# transciever.net
KiCad netlist of a schematic drawn in EAGLE
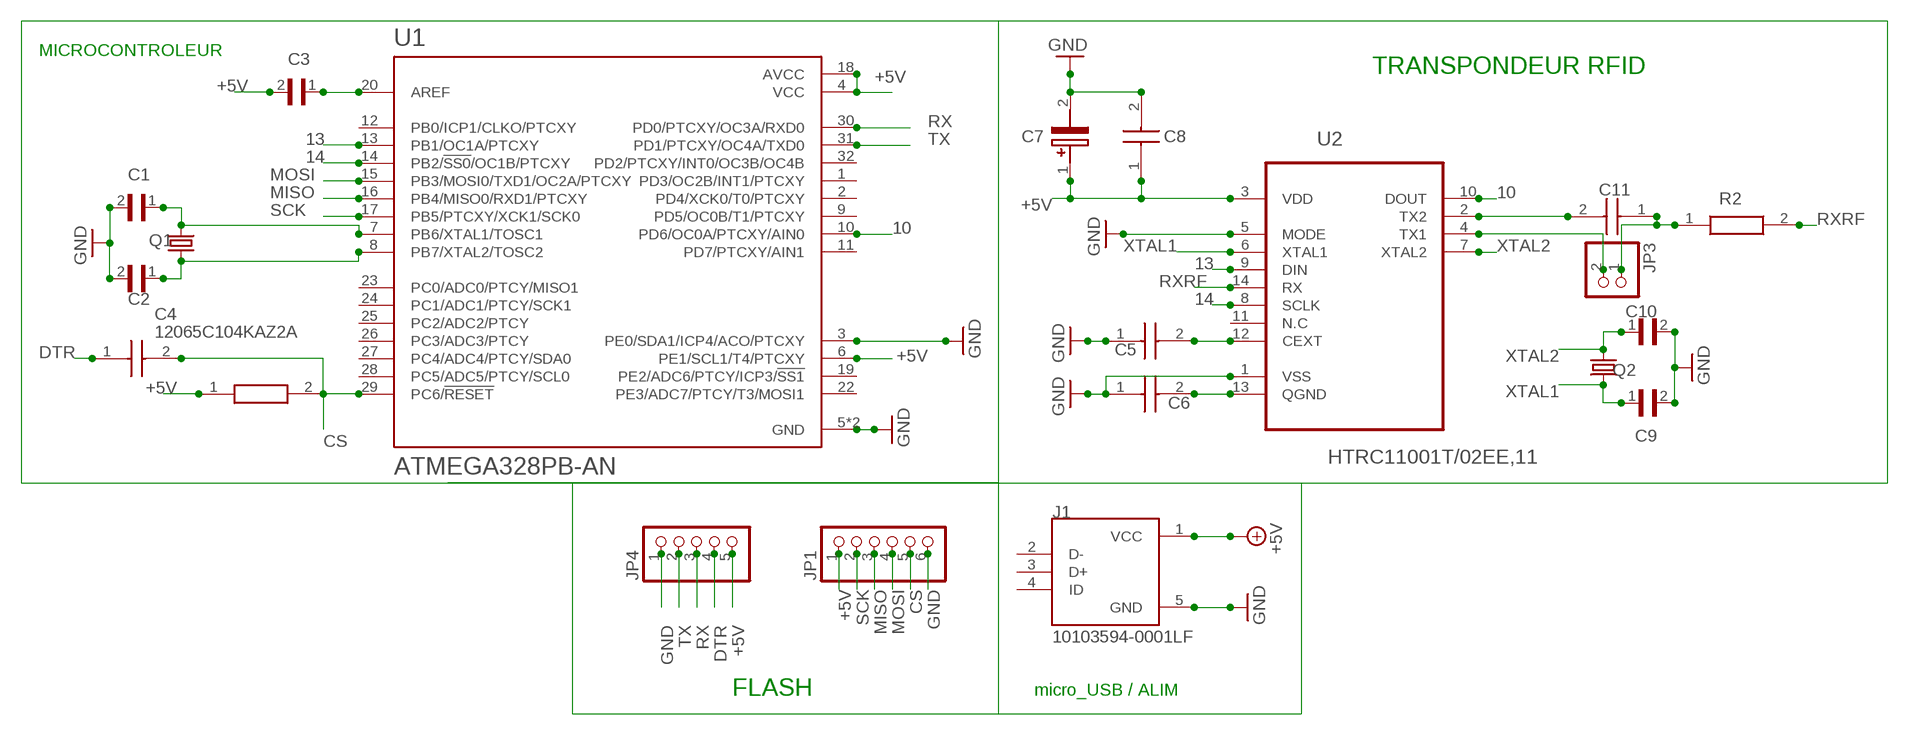
[diagram p0: schematic, sheet 1]

(export (version "E")
  (design (tool "Eeschema 10.0.6"))
  (components
    (comp (ref "C1")
      (value "06031U220GAT2A")
      (footprint "eagle-import:CAPC1608X90")
      (libsource (lib "eagle-import") (part "06031U220GAT2A"))
    )
    (comp (ref "C2")
      (value "06031U220GAT2A")
      (footprint "eagle-import:CAPC1608X90")
      (libsource (lib "eagle-import") (part "06031U220GAT2A"))
    )
    (comp (ref "C3")
      (value "GRT31CC80J476KE13L")
      (footprint "eagle-import:CAP3216X125N")
      (libsource (lib "eagle-import") (part "GRT31CC80J476KE13L"))
    )
    (comp (ref "C4")
      (value "12065C104KAZ2A")
      (footprint "eagle-import:CAPC3216X94N")
      (fields (field (name "RS_PART_NUMBER") "6983673"))
      (libsource (lib "eagle-import") (part "12065C104KAZ2A"))
    )
    (comp (ref "C5")
      (value "12065C104KAZ2A")
      (footprint "eagle-import:CAPC3216X94N")
      (fields (field (name "RS_PART_NUMBER") "6983673"))
      (libsource (lib "eagle-import") (part "12065C104KAZ2A"))
    )
    (comp (ref "C6")
      (value "12065C104KAZ2A")
      (footprint "eagle-import:CAPC3216X94N")
      (fields (field (name "RS_PART_NUMBER") "6983673"))
      (libsource (lib "eagle-import") (part "12065C104KAZ2A"))
    )
    (comp (ref "C7")
      (value "NACE100M16V4X5.5TR13F")
      (footprint "eagle-import:NACE(4X5.5)")
      (fields (field (name "RS_PART_NUMBER") "7379625P"))
      (libsource (lib "eagle-import") (part "NACE100M16V4X5.5TR13F"))
    )
    (comp (ref "C8")
      (value "12065C104KAZ2A")
      (footprint "eagle-import:CAPC3216X94N")
      (fields (field (name "RS_PART_NUMBER") "6983673"))
      (libsource (lib "eagle-import") (part "12065C104KAZ2A"))
    )
    (comp (ref "C9")
      (value "06031U220GAT2A")
      (footprint "eagle-import:CAPC1608X90")
      (libsource (lib "eagle-import") (part "06031U220GAT2A"))
    )
    (comp (ref "C10")
      (value "06031U220GAT2A")
      (footprint "eagle-import:CAPC1608X90")
      (libsource (lib "eagle-import") (part "06031U220GAT2A"))
    )
    (comp (ref "C11")
      (value "12065C104KAZ2A")
      (footprint "eagle-import:CAPC3216X94N")
      (fields (field (name "RS_PART_NUMBER") "6983673"))
      (libsource (lib "eagle-import") (part "12065C104KAZ2A"))
    )
    (comp (ref "J1")
      (value "10103594-0001LF")
      (footprint "eagle-import:FCI_10103594-0001LF")
      (fields (field (name "MANUFACTURER") "Framatome"))
      (libsource (lib "eagle-import") (part "10103594-0001LF"))
    )
    (comp (ref "JP1")
      (value "PINHD-1X6")
      (footprint "eagle-import:1X06")
      (libsource (lib "eagle-import") (part "PINHD-1X6"))
    )
    (comp (ref "JP3")
      (value "PINHD-1X2")
      (footprint "eagle-import:1X02")
      (libsource (lib "eagle-import") (part "PINHD-1X2"))
    )
    (comp (ref "JP4")
      (value "PINHD-1X5")
      (footprint "eagle-import:1X05")
      (libsource (lib "eagle-import") (part "PINHD-1X5"))
    )
    (comp (ref "Q1")
      (value "KX-K")
      (footprint "eagle-import:11.4X4.5")
      (libsource (lib "eagle-import") (part "KX-K"))
    )
    (comp (ref "Q2")
      (value "KX-K")
      (footprint "eagle-import:11.4X4.5")
      (libsource (lib "eagle-import") (part "KX-K"))
    )
    (comp (ref "R1")
      (value "CRCW12061K00FKEA")
      (footprint "eagle-import:RESC3216X60N")
      (fields (field (name "RS_PART_NUMBER") "1694817"))
      (libsource (lib "eagle-import") (part "CRCW12061K00FKEA"))
    )
    (comp (ref "R2")
      (value "CRCW12061K00FKEA")
      (footprint "eagle-import:RESC3216X60N")
      (fields (field (name "RS_PART_NUMBER") "1694817"))
      (libsource (lib "eagle-import") (part "CRCW12061K00FKEA"))
    )
    (comp (ref "U1")
      (value "ATMEGA328PB-AN")
      (footprint "eagle-import:QFP80P900X900X120-32N")
      (fields (field (name "MANUFACTURER") "Microchip"))
      (libsource (lib "eagle-import") (part "ATMEGA328PB-AN"))
    )
    (comp (ref "U2")
      (value "HTRC11001T/02EE,11")
      (footprint "eagle-import:SOIC127P600X175-14N")
      (libsource (lib "eagle-import") (part "HTRC11001T/02EE,11"))
    )
  )
  (nets
    (net (code "1") (name "+5V") (class "Default")
      (node (ref "C3") (pin "2") (pinfunction "2_2") (pintype "passive"))
      (node (ref "C7") (pin "1") (pinfunction "+_1") (pintype "bidirectional"))
      (node (ref "C8") (pin "1") (pinfunction "1_1") (pintype "bidirectional"))
      (node (ref "J1") (pin "1") (pinfunction "VCC_1") (pintype "power_in"))
      (node (ref "JP1") (pin "1") (pinfunction "1_1") (pintype "passive"))
      (node (ref "JP4") (pin "5") (pinfunction "5_5") (pintype "passive"))
      (node (ref "R1") (pin "1") (pinfunction "1_1") (pintype "bidirectional"))
      (node (ref "U1") (pin "18") (pinfunction "AVCC_18") (pintype "power_in"))
      (node (ref "U1") (pin "4") (pinfunction "VCC_4") (pintype "power_in"))
      (node (ref "U1") (pin "6") (pinfunction "PE1/SCL1/T4/PTCXY_6") (pintype "bidirectional"))
      (node (ref "U2") (pin "3") (pinfunction "VDD_3") (pintype "power_in"))
    )
    (net (code "2") (name "/10") (class "Default")
      (node (ref "U1") (pin "10") (pinfunction "PD6/OC0A/PTCXY/AIN0_10") (pintype "bidirectional"))
      (node (ref "U2") (pin "10") (pinfunction "DOUT_10") (pintype "output"))
    )
    (net (code "3") (name "/13") (class "Default")
      (node (ref "U1") (pin "13") (pinfunction "PB1/OC1A/PTCXY_13") (pintype "bidirectional"))
      (node (ref "U2") (pin "9") (pinfunction "DIN_9") (pintype "input"))
    )
    (net (code "4") (name "/14") (class "Default")
      (node (ref "U1") (pin "14") (pinfunction "PB2/~{SS0}/OC1B/PTCXY_14") (pintype "bidirectional"))
      (node (ref "U2") (pin "8") (pinfunction "SCLK_8") (pintype "input"))
    )
    (net (code "5") (name "/CS") (class "Default")
      (node (ref "C4") (pin "2") (pinfunction "2_2") (pintype "bidirectional"))
      (node (ref "JP1") (pin "5") (pinfunction "5_5") (pintype "passive"))
      (node (ref "R1") (pin "2") (pinfunction "2_2") (pintype "bidirectional"))
      (node (ref "U1") (pin "29") (pinfunction "PC6/~{RESET}_29") (pintype "bidirectional"))
    )
    (net (code "6") (name "/DTR") (class "Default")
      (node (ref "C4") (pin "1") (pinfunction "1_1") (pintype "bidirectional"))
      (node (ref "JP4") (pin "4") (pinfunction "4_4") (pintype "passive"))
    )
    (net (code "7") (name "/MISO") (class "Default")
      (node (ref "JP1") (pin "3") (pinfunction "3_3") (pintype "passive"))
      (node (ref "U1") (pin "16") (pinfunction "PB4/MISO0/RXD1/PTCXY_16") (pintype "bidirectional"))
    )
    (net (code "8") (name "/MOSI") (class "Default")
      (node (ref "JP1") (pin "4") (pinfunction "4_4") (pintype "passive"))
      (node (ref "U1") (pin "15") (pinfunction "PB3/MOSI0/TXD1/OC2A/PTCXY_15") (pintype "bidirectional"))
    )
    (net (code "9") (name "/RX") (class "Default")
      (node (ref "JP4") (pin "3") (pinfunction "3_3") (pintype "passive"))
      (node (ref "U1") (pin "30") (pinfunction "PD0/PTCXY/OC3A/RXD0_30") (pintype "bidirectional"))
    )
    (net (code "10") (name "/RXRF") (class "Default")
      (node (ref "R2") (pin "2") (pinfunction "2_2") (pintype "bidirectional"))
      (node (ref "U2") (pin "14") (pinfunction "RX_14") (pintype "input"))
    )
    (net (code "11") (name "/SCK") (class "Default")
      (node (ref "JP1") (pin "2") (pinfunction "2_2") (pintype "passive"))
      (node (ref "U1") (pin "17") (pinfunction "PB5/PTCXY/XCK1/SCK0_17") (pintype "bidirectional"))
    )
    (net (code "12") (name "/TX") (class "Default")
      (node (ref "JP4") (pin "2") (pinfunction "2_2") (pintype "passive"))
      (node (ref "U1") (pin "31") (pinfunction "PD1/PTCXY/OC4A/TXD0_31") (pintype "bidirectional"))
    )
    (net (code "13") (name "/XTAL1") (class "Default")
      (node (ref "C9") (pin "1") (pinfunction "1_1") (pintype "passive"))
      (node (ref "Q2") (pin "2") (pinfunction "2_2") (pintype "passive"))
      (node (ref "U2") (pin "6") (pinfunction "XTAL1_6") (pintype "input"))
    )
    (net (code "14") (name "/XTAL2") (class "Default")
      (node (ref "C10") (pin "1") (pinfunction "1_1") (pintype "passive"))
      (node (ref "Q2") (pin "1") (pinfunction "1_1") (pintype "passive"))
      (node (ref "U2") (pin "7") (pinfunction "XTAL2_7") (pintype "output"))
    )
    (net (code "15") (name "GND") (class "Default")
      (node (ref "C1") (pin "2") (pinfunction "2_2") (pintype "passive"))
      (node (ref "C10") (pin "2") (pinfunction "2_2") (pintype "passive"))
      (node (ref "C2") (pin "2") (pinfunction "2_2") (pintype "passive"))
      (node (ref "C5") (pin "1") (pinfunction "1_1") (pintype "bidirectional"))
      (node (ref "C6") (pin "1") (pinfunction "1_1") (pintype "bidirectional"))
      (node (ref "C7") (pin "2") (pinfunction "-_2") (pintype "bidirectional"))
      (node (ref "C8") (pin "2") (pinfunction "2_2") (pintype "bidirectional"))
      (node (ref "C9") (pin "2") (pinfunction "2_2") (pintype "passive"))
      (node (ref "J1") (pin "5") (pinfunction "GND_5") (pintype "power_in"))
      (node (ref "JP1") (pin "6") (pinfunction "6_6") (pintype "passive"))
      (node (ref "JP4") (pin "1") (pinfunction "1_1") (pintype "passive"))
      (node (ref "U1") (pin "21") (pinfunction "GND_21") (pintype "power_in"))
      (node (ref "U1") (pin "3") (pinfunction "PE0/SDA1/ICP4/ACO/PTCXY_3") (pintype "bidirectional"))
      (node (ref "U1") (pin "5") (pinfunction "GND_5") (pintype "power_in"))
      (node (ref "U2") (pin "1") (pinfunction "VSS_1") (pintype "power_in"))
      (node (ref "U2") (pin "5") (pinfunction "MODE_5") (pintype "output"))
    )
    (net (code "16") (name "Net-(C11-Pad1)") (class "Default")
      (node (ref "C11") (pin "1") (pinfunction "1_1") (pintype "bidirectional"))
      (node (ref "JP3") (pin "1") (pinfunction "1_1") (pintype "passive"))
      (node (ref "R2") (pin "1") (pinfunction "1_1") (pintype "bidirectional"))
    )
    (net (code "17") (name "Net-(U1-AREF)") (class "Default")
      (node (ref "C3") (pin "1") (pinfunction "1_1") (pintype "passive"))
      (node (ref "U1") (pin "20") (pinfunction "AREF_20") (pintype "input"))
    )
    (net (code "18") (name "Net-(U1-PB6{slash}XTAL1{slash}TOSC1)") (class "Default")
      (node (ref "C1") (pin "1") (pinfunction "1_1") (pintype "passive"))
      (node (ref "Q1") (pin "2") (pinfunction "2_2") (pintype "passive"))
      (node (ref "U1") (pin "7") (pinfunction "PB6/XTAL1/TOSC1_7") (pintype "bidirectional"))
    )
    (net (code "19") (name "Net-(U1-PB7{slash}XTAL2{slash}TOSC2)") (class "Default")
      (node (ref "C2") (pin "1") (pinfunction "1_1") (pintype "passive"))
      (node (ref "Q1") (pin "1") (pinfunction "1_1") (pintype "passive"))
      (node (ref "U1") (pin "8") (pinfunction "PB7/XTAL2/TOSC2_8") (pintype "bidirectional"))
    )
    (net (code "20") (name "Net-(U2-CEXT)") (class "Default")
      (node (ref "C5") (pin "2") (pinfunction "2_2") (pintype "bidirectional"))
      (node (ref "U2") (pin "12") (pinfunction "CEXT_12") (pintype "input"))
    )
    (net (code "21") (name "Net-(U2-QGND)") (class "Default")
      (node (ref "C6") (pin "2") (pinfunction "2_2") (pintype "bidirectional"))
      (node (ref "U2") (pin "13") (pinfunction "QGND_13") (pintype "passive"))
    )
    (net (code "22") (name "Net-(U2-TX1)") (class "Default")
      (node (ref "JP3") (pin "2") (pinfunction "2_2") (pintype "passive"))
      (node (ref "U2") (pin "4") (pinfunction "TX1_4") (pintype "passive"))
    )
    (net (code "23") (name "Net-(U2-TX2)") (class "Default")
      (node (ref "C11") (pin "2") (pinfunction "2_2") (pintype "bidirectional"))
      (node (ref "U2") (pin "2") (pinfunction "TX2_2") (pintype "output"))
    )
    (net (code "24") (name "unconnected-(J1-D+-Pad3)") (class "Default")
      (node (ref "J1") (pin "3") (pinfunction "D+_3") (pintype "bidirectional"))
    )
    (net (code "25") (name "unconnected-(J1-D--Pad2)") (class "Default")
      (node (ref "J1") (pin "2") (pinfunction "D-_2") (pintype "bidirectional"))
    )
    (net (code "26") (name "unconnected-(J1-ID-Pad4)") (class "Default")
      (node (ref "J1") (pin "4") (pinfunction "ID_4") (pintype "bidirectional"))
    )
    (net (code "27") (name "unconnected-(U1-PB0{slash}ICP1{slash}CLKO{slash}PTCXY-Pad12)") (class "Default")
      (node (ref "U1") (pin "12") (pinfunction "PB0/ICP1/CLKO/PTCXY_12") (pintype "bidirectional"))
    )
    (net (code "28") (name "unconnected-(U1-PC0{slash}ADC0{slash}PTCY{slash}MISO1-Pad23)") (class "Default")
      (node (ref "U1") (pin "23") (pinfunction "PC0/ADC0/PTCY/MISO1_23") (pintype "bidirectional"))
    )
    (net (code "29") (name "unconnected-(U1-PC1{slash}ADC1{slash}PTCY{slash}SCK1-Pad24)") (class "Default")
      (node (ref "U1") (pin "24") (pinfunction "PC1/ADC1/PTCY/SCK1_24") (pintype "bidirectional"))
    )
    (net (code "30") (name "unconnected-(U1-PC2{slash}ADC2{slash}PTCY-Pad25)") (class "Default")
      (node (ref "U1") (pin "25") (pinfunction "PC2/ADC2/PTCY_25") (pintype "bidirectional"))
    )
    (net (code "31") (name "unconnected-(U1-PC3{slash}ADC3{slash}PTCY-Pad26)") (class "Default")
      (node (ref "U1") (pin "26") (pinfunction "PC3/ADC3/PTCY_26") (pintype "bidirectional"))
    )
    (net (code "32") (name "unconnected-(U1-PC4{slash}ADC4{slash}PTCY{slash}SDA0-Pad27)") (class "Default")
      (node (ref "U1") (pin "27") (pinfunction "PC4/ADC4/PTCY/SDA0_27") (pintype "bidirectional"))
    )
    (net (code "33") (name "unconnected-(U1-PC5{slash}ADC5{slash}PTCY{slash}SCL0-Pad28)") (class "Default")
      (node (ref "U1") (pin "28") (pinfunction "PC5/ADC5/PTCY/SCL0_28") (pintype "bidirectional"))
    )
    (net (code "34") (name "unconnected-(U1-PD2{slash}PTCXY{slash}INT0{slash}OC3B{slash}OC4B-Pad32)") (class "Default")
      (node (ref "U1") (pin "32") (pinfunction "PD2/PTCXY/INT0/OC3B/OC4B_32") (pintype "bidirectional"))
    )
    (net (code "35") (name "unconnected-(U1-PD3{slash}OC2B{slash}INT1{slash}PTCXY-Pad1)") (class "Default")
      (node (ref "U1") (pin "1") (pinfunction "PD3/OC2B/INT1/PTCXY_1") (pintype "bidirectional"))
    )
    (net (code "36") (name "unconnected-(U1-PD4{slash}XCK0{slash}T0{slash}PTCXY-Pad2)") (class "Default")
      (node (ref "U1") (pin "2") (pinfunction "PD4/XCK0/T0/PTCXY_2") (pintype "bidirectional"))
    )
    (net (code "37") (name "unconnected-(U1-PD5{slash}OC0B{slash}T1{slash}PTCXY-Pad9)") (class "Default")
      (node (ref "U1") (pin "9") (pinfunction "PD5/OC0B/T1/PTCXY_9") (pintype "bidirectional"))
    )
    (net (code "38") (name "unconnected-(U1-PD7{slash}PTCXY{slash}AIN1-Pad11)") (class "Default")
      (node (ref "U1") (pin "11") (pinfunction "PD7/PTCXY/AIN1_11") (pintype "bidirectional"))
    )
    (net (code "39") (name "unconnected-(U1-PE2{slash}ADC6{slash}PTCY{slash}ICP3{slash}~{SS1}-Pad19)") (class "Default")
      (node (ref "U1") (pin "19") (pinfunction "PE2/ADC6/PTCY/ICP3/~{SS1}_19") (pintype "bidirectional"))
    )
    (net (code "40") (name "unconnected-(U1-PE3{slash}ADC7{slash}PTCY{slash}T3{slash}MOSI1-Pad22)") (class "Default")
      (node (ref "U1") (pin "22") (pinfunction "PE3/ADC7/PTCY/T3/MOSI1_22") (pintype "bidirectional"))
    )
    (net (code "41") (name "unconnected-(U2-N.C-Pad11)") (class "Default")
      (node (ref "U2") (pin "11") (pinfunction "N.C_11") (pintype "no_connect"))
    )
  )
)
